# lm2576_acs720_hc_020k.net
KiCad netlist of a schematic drawn in EAGLE
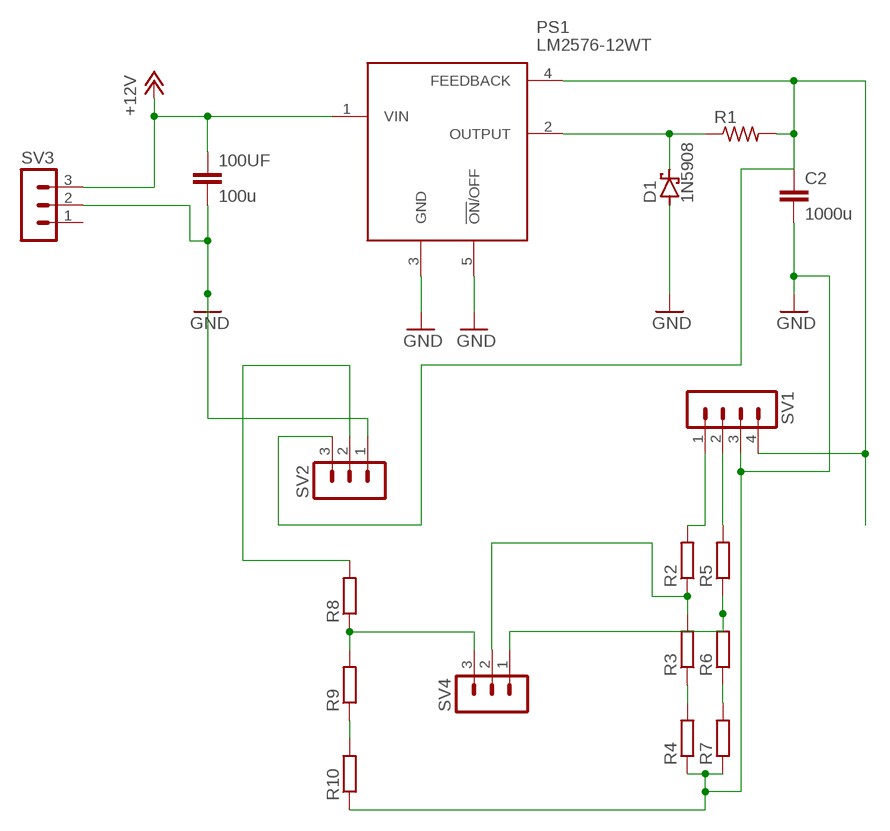
[diagram p0: schematic, sheet 1]

(export (version "E")
  (design (tool "Eeschema 10.0.6"))
  (components
    (comp (ref "100UF")
      (value "100u")
      (footprint "eagle-import:C5B5")
      (libsource (lib "eagle-import") (part "C5/5"))
    )
    (comp (ref "C2")
      (value "1000u")
      (footprint "eagle-import:C5B5")
      (libsource (lib "eagle-import") (part "C5/5"))
    )
    (comp (ref "D1")
      (value "1N5908")
      (footprint "eagle-import:C4111-15")
      (libsource (lib "eagle-import") (part "1N5908"))
    )
    (comp (ref "PS1")
      (value "LM2576-12WT")
      (footprint "eagle-import:TO170P470X1016X1900-5P")
      (fields (field (name "MOUSER_PART_NUMBER") "998-LM2576-12WT") (field (name "RS_PART_NUMBER") "1771883"))
      (libsource (lib "eagle-import") (part "LM2576-12WT"))
    )
    (comp (ref "R1")
      (value "R-US_VTA55")
      (footprint "eagle-import:VTA55")
      (libsource (lib "eagle-import") (part "R-US_VTA55"))
    )
    (comp (ref "R2")
      (value "R-EU_0207/12")
      (footprint "eagle-import:0207_12")
      (libsource (lib "eagle-import") (part "R-EU_0207/12"))
    )
    (comp (ref "R3")
      (value "R-EU_0207/12")
      (footprint "eagle-import:0207_12")
      (libsource (lib "eagle-import") (part "R-EU_0207/12"))
    )
    (comp (ref "R4")
      (value "R-EU_0207/12")
      (footprint "eagle-import:0207_12")
      (libsource (lib "eagle-import") (part "R-EU_0207/12"))
    )
    (comp (ref "R5")
      (value "R-EU_0207/12")
      (footprint "eagle-import:0207_12")
      (libsource (lib "eagle-import") (part "R-EU_0207/12"))
    )
    (comp (ref "R6")
      (value "R-EU_0207/12")
      (footprint "eagle-import:0207_12")
      (libsource (lib "eagle-import") (part "R-EU_0207/12"))
    )
    (comp (ref "R7")
      (value "R-EU_0207/12")
      (footprint "eagle-import:0207_12")
      (libsource (lib "eagle-import") (part "R-EU_0207/12"))
    )
    (comp (ref "R8")
      (value "R-EU_0207/12")
      (footprint "eagle-import:0207_12")
      (libsource (lib "eagle-import") (part "R-EU_0207/12"))
    )
    (comp (ref "R9")
      (value "R-EU_0207/12")
      (footprint "eagle-import:0207_12")
      (libsource (lib "eagle-import") (part "R-EU_0207/12"))
    )
    (comp (ref "R10")
      (value "R-EU_0207/12")
      (footprint "eagle-import:0207_12")
      (libsource (lib "eagle-import") (part "R-EU_0207/12"))
    )
    (comp (ref "SV1")
      (value "MA04-1")
      (footprint "eagle-import:MA04-1")
      (libsource (lib "eagle-import") (part "MA04-1"))
    )
    (comp (ref "SV2")
      (value "MA03-1")
      (footprint "eagle-import:MA03-1")
      (libsource (lib "eagle-import") (part "MA03-1"))
    )
    (comp (ref "SV3")
      (value "MA03-1")
      (footprint "eagle-import:MA03-1")
      (libsource (lib "eagle-import") (part "MA03-1"))
    )
    (comp (ref "SV4")
      (value "MA03-1")
      (footprint "eagle-import:MA03-1")
      (libsource (lib "eagle-import") (part "MA03-1"))
    )
  )
  (nets
    (net (code "1") (name "+12V") (class "Default")
      (node (ref "100UF") (pin "1") (pinfunction "1_1") (pintype "passive"))
      (node (ref "PS1") (pin "1") (pinfunction "VIN_1") (pintype "bidirectional"))
      (node (ref "SV3") (pin "3") (pinfunction "3_3") (pintype "passive"))
    )
    (net (code "2") (name "GND") (class "Default")
      (node (ref "100UF") (pin "2") (pinfunction "2_2") (pintype "passive"))
      (node (ref "C2") (pin "2") (pinfunction "2_2") (pintype "passive"))
      (node (ref "D1") (pin "A") (pinfunction "A_A") (pintype "passive"))
      (node (ref "PS1") (pin "3") (pinfunction "GND_3") (pintype "bidirectional"))
      (node (ref "PS1") (pin "5") (pinfunction "~{ON}/OFF_5") (pintype "bidirectional"))
      (node (ref "R10") (pin "1") (pinfunction "1_1") (pintype "passive"))
      (node (ref "R4") (pin "1") (pinfunction "1_1") (pintype "passive"))
      (node (ref "R7") (pin "1") (pinfunction "1_1") (pintype "passive"))
      (node (ref "SV1") (pin "3") (pinfunction "3_3") (pintype "passive"))
      (node (ref "SV2") (pin "1") (pinfunction "1_1") (pintype "passive"))
      (node (ref "SV3") (pin "2") (pinfunction "2_2") (pintype "passive"))
    )
    (net (code "3") (name "Net-(PS1-FEEDBACK)") (class "Default")
      (node (ref "C2") (pin "1") (pinfunction "1_1") (pintype "passive"))
      (node (ref "PS1") (pin "4") (pinfunction "FEEDBACK_4") (pintype "bidirectional"))
      (node (ref "R1") (pin "2") (pinfunction "2_2") (pintype "passive"))
      (node (ref "SV1") (pin "4") (pinfunction "4_4") (pintype "passive"))
      (node (ref "SV2") (pin "3") (pinfunction "3_3") (pintype "passive"))
    )
    (net (code "4") (name "Net-(PS1-OUTPUT)") (class "Default")
      (node (ref "D1") (pin "C") (pinfunction "C_C") (pintype "passive"))
      (node (ref "PS1") (pin "2") (pinfunction "OUTPUT_2") (pintype "bidirectional"))
      (node (ref "R1") (pin "1") (pinfunction "1_1") (pintype "passive"))
    )
    (net (code "5") (name "Net-(R2-Pad1)") (class "Default")
      (node (ref "R2") (pin "1") (pinfunction "1_1") (pintype "passive"))
      (node (ref "R3") (pin "2") (pinfunction "2_2") (pintype "passive"))
      (node (ref "SV4") (pin "2") (pinfunction "2_2") (pintype "passive"))
    )
    (net (code "6") (name "Net-(R2-Pad2)") (class "Default")
      (node (ref "R2") (pin "2") (pinfunction "2_2") (pintype "passive"))
      (node (ref "SV1") (pin "1") (pinfunction "1_1") (pintype "passive"))
    )
    (net (code "7") (name "Net-(R3-Pad1)") (class "Default")
      (node (ref "R3") (pin "1") (pinfunction "1_1") (pintype "passive"))
      (node (ref "R4") (pin "2") (pinfunction "2_2") (pintype "passive"))
    )
    (net (code "8") (name "Net-(R5-Pad1)") (class "Default")
      (node (ref "R5") (pin "1") (pinfunction "1_1") (pintype "passive"))
      (node (ref "R6") (pin "2") (pinfunction "2_2") (pintype "passive"))
      (node (ref "SV4") (pin "1") (pinfunction "1_1") (pintype "passive"))
    )
    (net (code "9") (name "Net-(R5-Pad2)") (class "Default")
      (node (ref "R5") (pin "2") (pinfunction "2_2") (pintype "passive"))
      (node (ref "SV1") (pin "2") (pinfunction "2_2") (pintype "passive"))
    )
    (net (code "10") (name "Net-(R6-Pad1)") (class "Default")
      (node (ref "R6") (pin "1") (pinfunction "1_1") (pintype "passive"))
      (node (ref "R7") (pin "2") (pinfunction "2_2") (pintype "passive"))
    )
    (net (code "11") (name "Net-(R8-Pad1)") (class "Default")
      (node (ref "R8") (pin "1") (pinfunction "1_1") (pintype "passive"))
      (node (ref "R9") (pin "2") (pinfunction "2_2") (pintype "passive"))
      (node (ref "SV4") (pin "3") (pinfunction "3_3") (pintype "passive"))
    )
    (net (code "12") (name "Net-(R8-Pad2)") (class "Default")
      (node (ref "R8") (pin "2") (pinfunction "2_2") (pintype "passive"))
      (node (ref "SV2") (pin "2") (pinfunction "2_2") (pintype "passive"))
    )
    (net (code "13") (name "Net-(R10-Pad2)") (class "Default")
      (node (ref "R10") (pin "2") (pinfunction "2_2") (pintype "passive"))
      (node (ref "R9") (pin "1") (pinfunction "1_1") (pintype "passive"))
    )
    (net (code "14") (name "unconnected-(SV3-Pad1)") (class "Default")
      (node (ref "SV3") (pin "1") (pinfunction "1_1") (pintype "passive"))
    )
  )
)
